# power_splitter.net
KiCad netlist of a schematic drawn in EAGLE
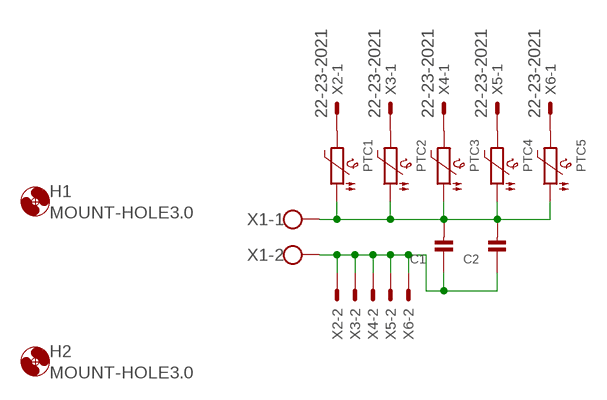
[diagram p0: schematic, sheet 1]

(export (version "E")
  (design (tool "Eeschema 10.0.6"))
  (components
    (comp (ref "C1")
      (value "CAP_CERAMIC_0805")
      (footprint "eagle-import:_0805")
      (libsource (lib "eagle-import") (part "CAP_CERAMIC_0805"))
    )
    (comp (ref "C2")
      (value "CAP_CERAMIC_0805")
      (footprint "eagle-import:_0805")
      (libsource (lib "eagle-import") (part "CAP_CERAMIC_0805"))
    )
    (comp (ref "H1")
      (value "MOUNT-HOLE3.0")
      (footprint "eagle-import:3,0")
      (libsource (lib "eagle-import") (part "MOUNT-HOLE3.0"))
    )
    (comp (ref "H2")
      (value "MOUNT-HOLE3.0")
      (footprint "eagle-import:3,0")
      (libsource (lib "eagle-import") (part "MOUNT-HOLE3.0"))
    )
    (comp (ref "PTC1")
      (value "PTC1206")
      (footprint "eagle-import:1206")
      (libsource (lib "eagle-import") (part "PTC1206"))
    )
    (comp (ref "PTC2")
      (value "PTC1206")
      (footprint "eagle-import:1206")
      (libsource (lib "eagle-import") (part "PTC1206"))
    )
    (comp (ref "PTC3")
      (value "PTC1206")
      (footprint "eagle-import:1206")
      (libsource (lib "eagle-import") (part "PTC1206"))
    )
    (comp (ref "PTC4")
      (value "PTC1206")
      (footprint "eagle-import:1206")
      (libsource (lib "eagle-import") (part "PTC1206"))
    )
    (comp (ref "PTC5")
      (value "PTC1206")
      (footprint "eagle-import:1206")
      (libsource (lib "eagle-import") (part "PTC1206"))
    )
    (comp (ref "X1")
      (value "W237-102")
      (footprint "eagle-import:W237-102")
      (fields (field (name "MPN") "237-102"))
      (libsource (lib "eagle-import") (part "W237-102"))
    )
    (comp (ref "X2")
      (value "22-23-2021")
      (footprint "eagle-import:22-23-2021")
      (fields (field (name "MF") "MOLEX"))
      (libsource (lib "eagle-import") (part "22-23-2021"))
    )
    (comp (ref "X3")
      (value "22-23-2021")
      (footprint "eagle-import:22-23-2021")
      (fields (field (name "MF") "MOLEX"))
      (libsource (lib "eagle-import") (part "22-23-2021"))
    )
    (comp (ref "X4")
      (value "22-23-2021")
      (footprint "eagle-import:22-23-2021")
      (fields (field (name "MF") "MOLEX"))
      (libsource (lib "eagle-import") (part "22-23-2021"))
    )
    (comp (ref "X5")
      (value "22-23-2021")
      (footprint "eagle-import:22-23-2021")
      (fields (field (name "MF") "MOLEX"))
      (libsource (lib "eagle-import") (part "22-23-2021"))
    )
    (comp (ref "X6")
      (value "22-23-2021")
      (footprint "eagle-import:22-23-2021")
      (fields (field (name "MF") "MOLEX"))
      (libsource (lib "eagle-import") (part "22-23-2021"))
    )
  )
  (nets
    (net (code "1") (name "Net-(C1-P$1)") (class "Default")
      (node (ref "C1") (pin "1") (pinfunction "P$1_1") (pintype "passive"))
      (node (ref "C2") (pin "1") (pinfunction "P$1_1") (pintype "passive"))
      (node (ref "X1") (pin "2") (pinfunction "KL_2") (pintype "passive"))
      (node (ref "X2") (pin "2") (pinfunction "S_2") (pintype "passive"))
      (node (ref "X3") (pin "2") (pinfunction "S_2") (pintype "passive"))
      (node (ref "X4") (pin "2") (pinfunction "S_2") (pintype "passive"))
      (node (ref "X5") (pin "2") (pinfunction "S_2") (pintype "passive"))
      (node (ref "X6") (pin "2") (pinfunction "S_2") (pintype "passive"))
    )
    (net (code "2") (name "Net-(C1-P$2)") (class "Default")
      (node (ref "C1") (pin "2") (pinfunction "P$2_2") (pintype "passive"))
      (node (ref "C2") (pin "2") (pinfunction "P$2_2") (pintype "passive"))
      (node (ref "PTC1") (pin "1") (pinfunction "1_1") (pintype "passive"))
      (node (ref "PTC2") (pin "1") (pinfunction "1_1") (pintype "passive"))
      (node (ref "PTC3") (pin "1") (pinfunction "1_1") (pintype "passive"))
      (node (ref "PTC4") (pin "1") (pinfunction "1_1") (pintype "passive"))
      (node (ref "PTC5") (pin "1") (pinfunction "1_1") (pintype "passive"))
      (node (ref "X1") (pin "1") (pinfunction "KL_1") (pintype "passive"))
    )
    (net (code "3") (name "Net-(X2A-S)") (class "Default")
      (node (ref "PTC1") (pin "2") (pinfunction "2_2") (pintype "passive"))
      (node (ref "X2") (pin "1") (pinfunction "S_1") (pintype "passive"))
    )
    (net (code "4") (name "Net-(X3A-S)") (class "Default")
      (node (ref "PTC2") (pin "2") (pinfunction "2_2") (pintype "passive"))
      (node (ref "X3") (pin "1") (pinfunction "S_1") (pintype "passive"))
    )
    (net (code "5") (name "Net-(X4A-S)") (class "Default")
      (node (ref "PTC3") (pin "2") (pinfunction "2_2") (pintype "passive"))
      (node (ref "X4") (pin "1") (pinfunction "S_1") (pintype "passive"))
    )
    (net (code "6") (name "Net-(X5A-S)") (class "Default")
      (node (ref "PTC4") (pin "2") (pinfunction "2_2") (pintype "passive"))
      (node (ref "X5") (pin "1") (pinfunction "S_1") (pintype "passive"))
    )
    (net (code "7") (name "Net-(X6A-S)") (class "Default")
      (node (ref "PTC5") (pin "2") (pinfunction "2_2") (pintype "passive"))
      (node (ref "X6") (pin "1") (pinfunction "S_1") (pintype "passive"))
    )
  )
)
